# NwazetRelayModule.net
KiCad netlist of a schematic drawn in EAGLE
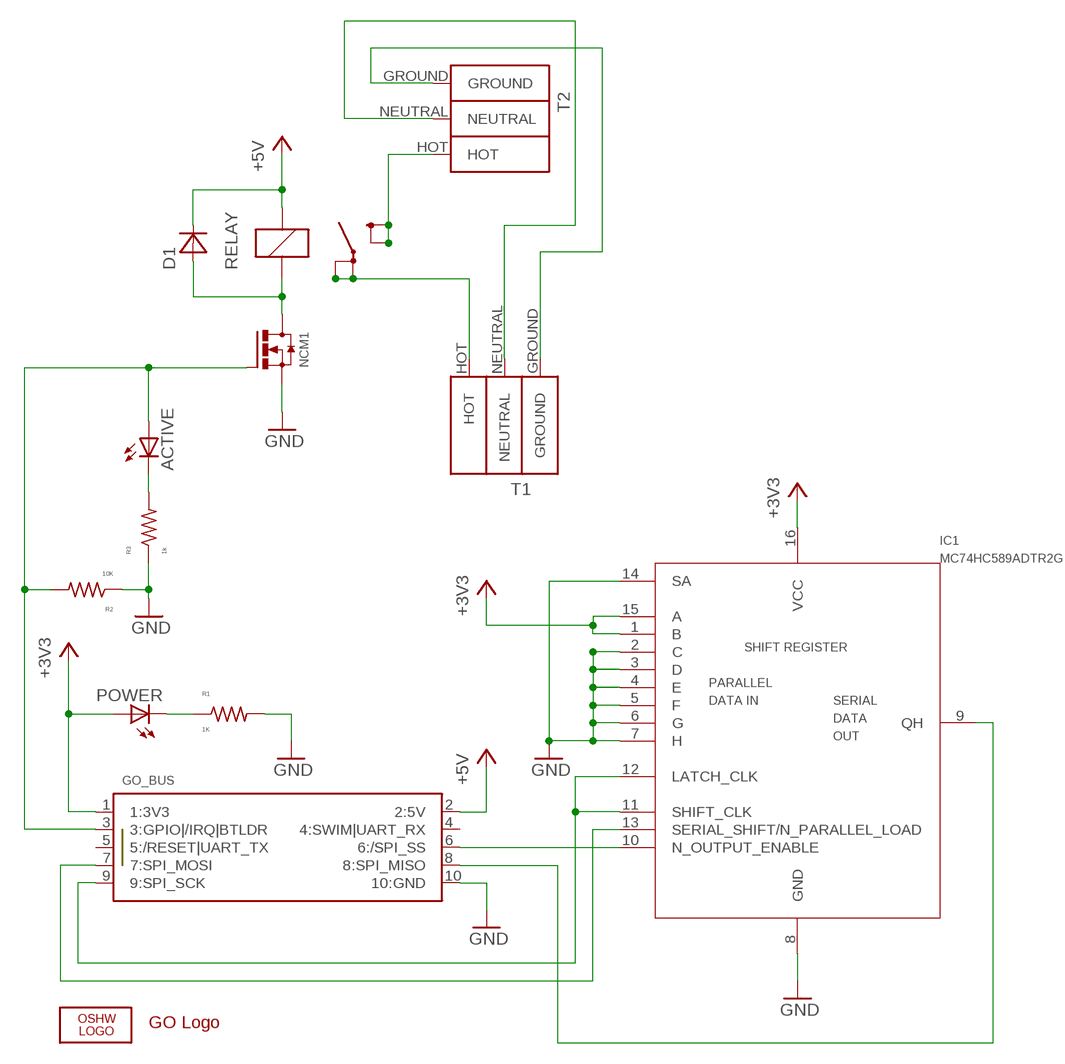
[diagram p0: schematic, sheet 1]

(export (version "E")
  (design (tool "Eeschema 10.0.6"))
  (components
    (comp (ref "ACTIVE")
      (value "LITEON_WHITE_LED_0805")
      (footprint "eagle-import:0805")
      (libsource (lib "eagle-import") (part "LITEON_WHITE_LED_0805"))
    )
    (comp (ref "D1")
      (value "DIODE_POWERDI_323")
      (footprint "eagle-import:DIODE_POWER_DI_323")
      (libsource (lib "eagle-import") (part "DIODE_POWERDI_323"))
    )
    (comp (ref "GO_BUS")
      (value "GO_CONNECTOR")
      (footprint "eagle-import:FCI-1.27X1.27MM_10PIN_HEADER_SHROUDED_SMT")
      (libsource (lib "eagle-import") (part "GO_CONNECTOR"))
    )
    (comp (ref "IC1")
      (value "MC74HC589ADTR2G")
      (footprint "eagle-import:MC74HC589ADTR2G")
      (libsource (lib "eagle-import") (part "MC74HC589ADTR2G"))
    )
    (comp (ref "LOGO1")
      (value "OSHW_LOGO_FILLX0100-NT")
      (footprint "eagle-import:OSHW_FILLX100_NOTEXT")
      (libsource (lib "eagle-import") (part "OSHW_LOGO_FILLX0100-NT"))
    )
    (comp (ref "NCM1")
      (value "PHILIPS_2N7002F_N_CHANNEL_MOSFET")
      (footprint "eagle-import:SOT23")
      (libsource (lib "eagle-import") (part "PHILIPS_2N7002F_N_CHANNEL_MOSFET"))
    )
    (comp (ref "POWER")
      (value "LITEON_WHITE_LED_0805")
      (footprint "eagle-import:0805")
      (libsource (lib "eagle-import") (part "LITEON_WHITE_LED_0805"))
    )
    (comp (ref "R1")
      (value "1K")
      (footprint "eagle-import:0805")
      (libsource (lib "eagle-import") (part "RESISTOR_0805"))
    )
    (comp (ref "R2")
      (value "10K")
      (footprint "eagle-import:0805")
      (libsource (lib "eagle-import") (part "RESISTOR_0805"))
    )
    (comp (ref "R3")
      (value "1k")
      (footprint "eagle-import:0805")
      (libsource (lib "eagle-import") (part "RESISTOR_0805"))
    )
    (comp (ref "RELAY")
      (value "SCHRACK_POWER_PCB_RELAY_RZ_16A_NO")
      (footprint "eagle-import:SCHRACK_POWER_PCB_RELAY_RZ_16A")
      (libsource (lib "eagle-import") (part "SCHRACK_POWER_PCB_RELAY_RZ_16A_NO"))
    )
    (comp (ref "T1")
      (value "PHOENIX_WIRE_CONTACT_3_POSITIONS")
      (footprint "eagle-import:WIRE_CONTACT_3_POSITIONS")
      (libsource (lib "eagle-import") (part "PHOENIX_WIRE_CONTACT_3_POSITIONS"))
    )
    (comp (ref "T2")
      (value "PHOENIX_WIRE_CONTACT_3_POSITIONS")
      (footprint "eagle-import:WIRE_CONTACT_3_POSITIONS")
      (libsource (lib "eagle-import") (part "PHOENIX_WIRE_CONTACT_3_POSITIONS"))
    )
    (comp (ref "U$8")
      (value "GO_LOGO")
      (footprint "eagle-import:GO_LOGO")
      (libsource (lib "eagle-import") (part "GO_LOGO"))
    )
  )
  (nets
    (net (code "1") (name "+3V3") (class "Default")
      (node (ref "GO_BUS") (pin "1") (pinfunction "1:3V3_1") (pintype "power_in"))
      (node (ref "IC1") (pin "1") (pinfunction "B_1") (pintype "bidirectional"))
      (node (ref "IC1") (pin "15") (pinfunction "A_15") (pintype "bidirectional"))
      (node (ref "IC1") (pin "16") (pinfunction "VCC_16") (pintype "bidirectional"))
      (node (ref "POWER") (pin "A") (pinfunction "A_A") (pintype "passive"))
    )
    (net (code "2") (name "+5V") (class "Default")
      (node (ref "D1") (pin "CATHODE") (pinfunction "C_CATHODE") (pintype "passive"))
      (node (ref "GO_BUS") (pin "2") (pinfunction "2:5V_2") (pintype "power_in"))
      (node (ref "RELAY") (pin "COIL_A1") (pinfunction "COIL_A1_COIL_A1") (pintype "passive"))
    )
    (net (code "3") (name "GND") (class "Default")
      (node (ref "GO_BUS") (pin "10") (pinfunction "10:GND_10") (pintype "passive"))
      (node (ref "IC1") (pin "14") (pinfunction "SA_14") (pintype "bidirectional"))
      (node (ref "IC1") (pin "2") (pinfunction "C_2") (pintype "bidirectional"))
      (node (ref "IC1") (pin "3") (pinfunction "D_3") (pintype "bidirectional"))
      (node (ref "IC1") (pin "4") (pinfunction "E_4") (pintype "bidirectional"))
      (node (ref "IC1") (pin "5") (pinfunction "F_5") (pintype "bidirectional"))
      (node (ref "IC1") (pin "6") (pinfunction "G_6") (pintype "bidirectional"))
      (node (ref "IC1") (pin "7") (pinfunction "H_7") (pintype "bidirectional"))
      (node (ref "IC1") (pin "8") (pinfunction "GND_8") (pintype "bidirectional"))
      (node (ref "NCM1") (pin "2_SOURCE") (pinfunction "SOURCE_2_SOURCE") (pintype "passive"))
      (node (ref "R1") (pin "K") (pinfunction "2_K") (pintype "passive"))
      (node (ref "R2") (pin "A") (pinfunction "1_A") (pintype "passive"))
      (node (ref "R3") (pin "A") (pinfunction "1_A") (pintype "passive"))
    )
    (net (code "4") (name "Net-(ACTIVE-C)") (class "Default")
      (node (ref "ACTIVE") (pin "K") (pinfunction "C_K") (pintype "passive"))
      (node (ref "R3") (pin "K") (pinfunction "2_K") (pintype "passive"))
    )
    (net (code "5") (name "Net-(D1-A)") (class "Default")
      (node (ref "D1") (pin "ANODE") (pinfunction "A_ANODE") (pintype "passive"))
      (node (ref "NCM1") (pin "3_DRAIN") (pinfunction "DRAIN_3_DRAIN") (pintype "passive"))
      (node (ref "RELAY") (pin "COIL_A2") (pinfunction "COIL_A2_COIL_A2") (pintype "passive"))
    )
    (net (code "6") (name "Net-(GO_BUS-3:GPIO|{slash}IRQ|BTLDR)") (class "Default")
      (node (ref "ACTIVE") (pin "A") (pinfunction "A_A") (pintype "passive"))
      (node (ref "GO_BUS") (pin "3") (pinfunction "3:GPIO|/IRQ|BTLDR_3") (pintype "bidirectional"))
      (node (ref "NCM1") (pin "1_GATE") (pinfunction "GATE_1_GATE") (pintype "passive"))
      (node (ref "R2") (pin "K") (pinfunction "2_K") (pintype "passive"))
    )
    (net (code "7") (name "Net-(GO_BUS-6:{slash}SPI_SS)") (class "Default")
      (node (ref "GO_BUS") (pin "6") (pinfunction "6:/SPI_SS_6") (pintype "bidirectional"))
      (node (ref "IC1") (pin "10") (pinfunction "N_OUTPUT_ENABLE_10") (pintype "bidirectional"))
    )
    (net (code "8") (name "Net-(GO_BUS-7:SPI_MOSI)") (class "Default")
      (node (ref "GO_BUS") (pin "7") (pinfunction "7:SPI_MOSI_7") (pintype "bidirectional"))
      (node (ref "IC1") (pin "13") (pinfunction "SERIAL_SHIFT/N_PARALLEL_LOAD_13") (pintype "bidirectional"))
    )
    (net (code "9") (name "Net-(GO_BUS-8:SPI_MISO)") (class "Default")
      (node (ref "GO_BUS") (pin "8") (pinfunction "8:SPI_MISO_8") (pintype "bidirectional"))
      (node (ref "IC1") (pin "9") (pinfunction "QH_9") (pintype "bidirectional"))
    )
    (net (code "10") (name "Net-(GO_BUS-9:SPI_SCK)") (class "Default")
      (node (ref "GO_BUS") (pin "9") (pinfunction "9:SPI_SCK_9") (pintype "bidirectional"))
      (node (ref "IC1") (pin "11") (pinfunction "SHIFT_CLK_11") (pintype "bidirectional"))
      (node (ref "IC1") (pin "12") (pinfunction "LATCH_CLK_12") (pintype "bidirectional"))
    )
    (net (code "11") (name "Net-(POWER-C)") (class "Default")
      (node (ref "POWER") (pin "K") (pinfunction "C_K") (pintype "passive"))
      (node (ref "R1") (pin "A") (pinfunction "1_A") (pintype "passive"))
    )
    (net (code "12") (name "Net-(RELAY-Pad11A_LOAD)") (class "Default")
      (node (ref "RELAY") (pin "11A_LOAD") (pinfunction "11A_LOAD_11A_LOAD") (pintype "passive"))
      (node (ref "RELAY") (pin "11B_LOAD") (pinfunction "11B_LOAD_11B_LOAD") (pintype "passive"))
      (node (ref "T1") (pin "HOT") (pinfunction "HOT_HOT") (pintype "power_in"))
    )
    (net (code "13") (name "Net-(RELAY-Pad14A_LOAD)") (class "Default")
      (node (ref "RELAY") (pin "14A_LOAD") (pinfunction "14A_LOAD_14A_LOAD") (pintype "passive"))
      (node (ref "RELAY") (pin "14B_LOAD") (pinfunction "14B_LOAD_14B_LOAD") (pintype "passive"))
      (node (ref "T2") (pin "HOT") (pinfunction "HOT_HOT") (pintype "power_in"))
    )
    (net (code "14") (name "Net-(T1-PadGROUND)") (class "Default")
      (node (ref "T1") (pin "GROUND") (pinfunction "GROUND_GROUND") (pintype "passive"))
      (node (ref "T2") (pin "GROUND") (pinfunction "GROUND_GROUND") (pintype "passive"))
    )
    (net (code "15") (name "Net-(T1-PadNEUTRAL)") (class "Default")
      (node (ref "T1") (pin "NEUTRAL") (pinfunction "NEUTRAL_NEUTRAL") (pintype "passive"))
      (node (ref "T2") (pin "NEUTRAL") (pinfunction "NEUTRAL_NEUTRAL") (pintype "passive"))
    )
    (net (code "16") (name "unconnected-(GO_BUS-4:SWIM|UART_RX-Pad4)") (class "Default")
      (node (ref "GO_BUS") (pin "4") (pinfunction "4:SWIM|UART_RX_4") (pintype "bidirectional"))
    )
    (net (code "17") (name "unconnected-(GO_BUS-5:{slash}RESET|UART_TX-Pad5)") (class "Default")
      (node (ref "GO_BUS") (pin "5") (pinfunction "5:/RESET|UART_TX_5") (pintype "bidirectional"))
    )
  )
)
